# MAX11609EEE-Breakout-Board-doubleHeaders.net
KiCad netlist of a schematic drawn in EAGLE
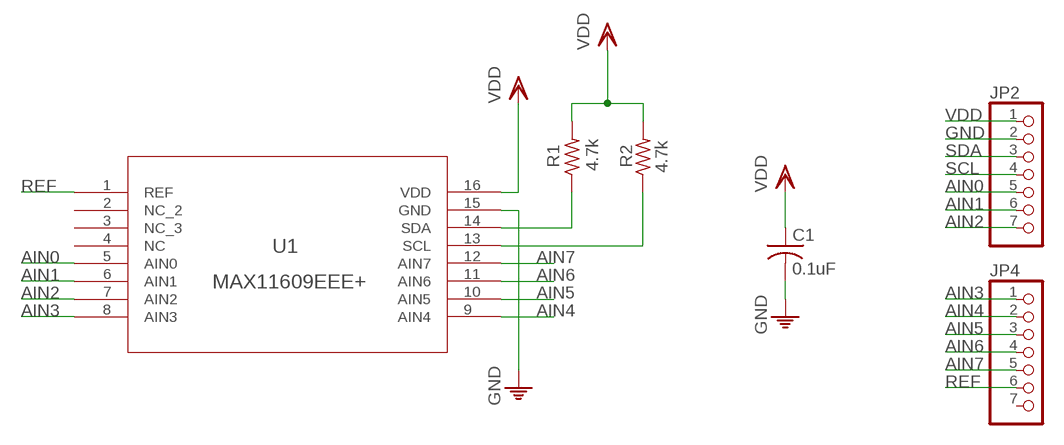
[diagram p0: schematic, sheet 1]

(export (version "E")
  (design (tool "Eeschema 10.0.6"))
  (components
    (comp (ref "C1")
      (value "0.1uF")
      (footprint "eagle-import:C0805")
      (libsource (lib "eagle-import") (part "C-USC0805"))
    )
    (comp (ref "JP2")
      (value "PINHD-1X7")
      (footprint "eagle-import:1X07")
      (libsource (lib "eagle-import") (part "PINHD-1X7"))
    )
    (comp (ref "JP4")
      (value "PINHD-1X7")
      (footprint "eagle-import:1X07")
      (libsource (lib "eagle-import") (part "PINHD-1X7"))
    )
    (comp (ref "R1")
      (value "4.7k")
      (footprint "eagle-import:R0805")
      (libsource (lib "eagle-import") (part "R-US_R0805"))
    )
    (comp (ref "R2")
      (value "4.7k")
      (footprint "eagle-import:R0805")
      (libsource (lib "eagle-import") (part "R-US_R0805"))
    )
    (comp (ref "U1")
      (value "MAX11609EEE+")
      (footprint "eagle-import:21-0055H_16")
      (libsource (lib "eagle-import") (part "MAX11609EEE+"))
    )
  )
  (nets
    (net (code "1") (name "/AIN0") (class "Default")
      (node (ref "JP2") (pin "5") (pinfunction "5_5") (pintype "passive"))
      (node (ref "U1") (pin "5") (pinfunction "AIN0_5") (pintype "input"))
    )
    (net (code "2") (name "/AIN1") (class "Default")
      (node (ref "JP2") (pin "6") (pinfunction "6_6") (pintype "passive"))
      (node (ref "U1") (pin "6") (pinfunction "AIN1_6") (pintype "input"))
    )
    (net (code "3") (name "/AIN2") (class "Default")
      (node (ref "JP2") (pin "7") (pinfunction "7_7") (pintype "passive"))
      (node (ref "U1") (pin "7") (pinfunction "AIN2_7") (pintype "input"))
    )
    (net (code "4") (name "/AIN3") (class "Default")
      (node (ref "JP4") (pin "1") (pinfunction "1_1") (pintype "passive"))
      (node (ref "U1") (pin "8") (pinfunction "AIN3_8") (pintype "input"))
    )
    (net (code "5") (name "/AIN4") (class "Default")
      (node (ref "JP4") (pin "2") (pinfunction "2_2") (pintype "passive"))
      (node (ref "U1") (pin "9") (pinfunction "AIN4_9") (pintype "input"))
    )
    (net (code "6") (name "/AIN5") (class "Default")
      (node (ref "JP4") (pin "3") (pinfunction "3_3") (pintype "passive"))
      (node (ref "U1") (pin "10") (pinfunction "AIN5_10") (pintype "input"))
    )
    (net (code "7") (name "/AIN6") (class "Default")
      (node (ref "JP4") (pin "4") (pinfunction "4_4") (pintype "passive"))
      (node (ref "U1") (pin "11") (pinfunction "AIN6_11") (pintype "input"))
    )
    (net (code "8") (name "/AIN7") (class "Default")
      (node (ref "JP4") (pin "5") (pinfunction "5_5") (pintype "passive"))
      (node (ref "U1") (pin "12") (pinfunction "AIN7_12") (pintype "input"))
    )
    (net (code "9") (name "/REF") (class "Default")
      (node (ref "JP4") (pin "6") (pinfunction "6_6") (pintype "passive"))
      (node (ref "U1") (pin "1") (pinfunction "REF_1") (pintype "passive"))
    )
    (net (code "10") (name "/SCL") (class "Default")
      (node (ref "JP2") (pin "4") (pinfunction "4_4") (pintype "passive"))
      (node (ref "R2") (pin "1") (pinfunction "1_1") (pintype "passive"))
      (node (ref "U1") (pin "13") (pinfunction "SCL_13") (pintype "passive"))
    )
    (net (code "11") (name "/SDA") (class "Default")
      (node (ref "JP2") (pin "3") (pinfunction "3_3") (pintype "passive"))
      (node (ref "R1") (pin "1") (pinfunction "1_1") (pintype "passive"))
      (node (ref "U1") (pin "14") (pinfunction "SDA_14") (pintype "passive"))
    )
    (net (code "12") (name "GND") (class "Default")
      (node (ref "C1") (pin "2") (pinfunction "2_2") (pintype "passive"))
      (node (ref "JP2") (pin "2") (pinfunction "2_2") (pintype "passive"))
      (node (ref "U1") (pin "15") (pinfunction "GND_15") (pintype "power_in"))
    )
    (net (code "13") (name "VDD") (class "Default")
      (node (ref "C1") (pin "1") (pinfunction "1_1") (pintype "passive"))
      (node (ref "JP2") (pin "1") (pinfunction "1_1") (pintype "passive"))
      (node (ref "R1") (pin "2") (pinfunction "2_2") (pintype "passive"))
      (node (ref "R2") (pin "2") (pinfunction "2_2") (pintype "passive"))
      (node (ref "U1") (pin "16") (pinfunction "VDD_16") (pintype "power_in"))
    )
    (net (code "14") (name "unconnected-(JP4-Pad7)") (class "Default")
      (node (ref "JP4") (pin "7") (pinfunction "7_7") (pintype "passive"))
    )
    (net (code "15") (name "unconnected-(U1-NC-Pad4)") (class "Default")
      (node (ref "U1") (pin "4") (pinfunction "NC_4") (pintype "passive"))
    )
    (net (code "16") (name "unconnected-(U1-NC_2-Pad2)") (class "Default")
      (node (ref "U1") (pin "2") (pinfunction "NC_2_2") (pintype "passive"))
    )
    (net (code "17") (name "unconnected-(U1-NC_3-Pad3)") (class "Default")
      (node (ref "U1") (pin "3") (pinfunction "NC_3_3") (pintype "passive"))
    )
  )
)
